# m1-control.net
KiCad netlist of a schematic drawn in EAGLE
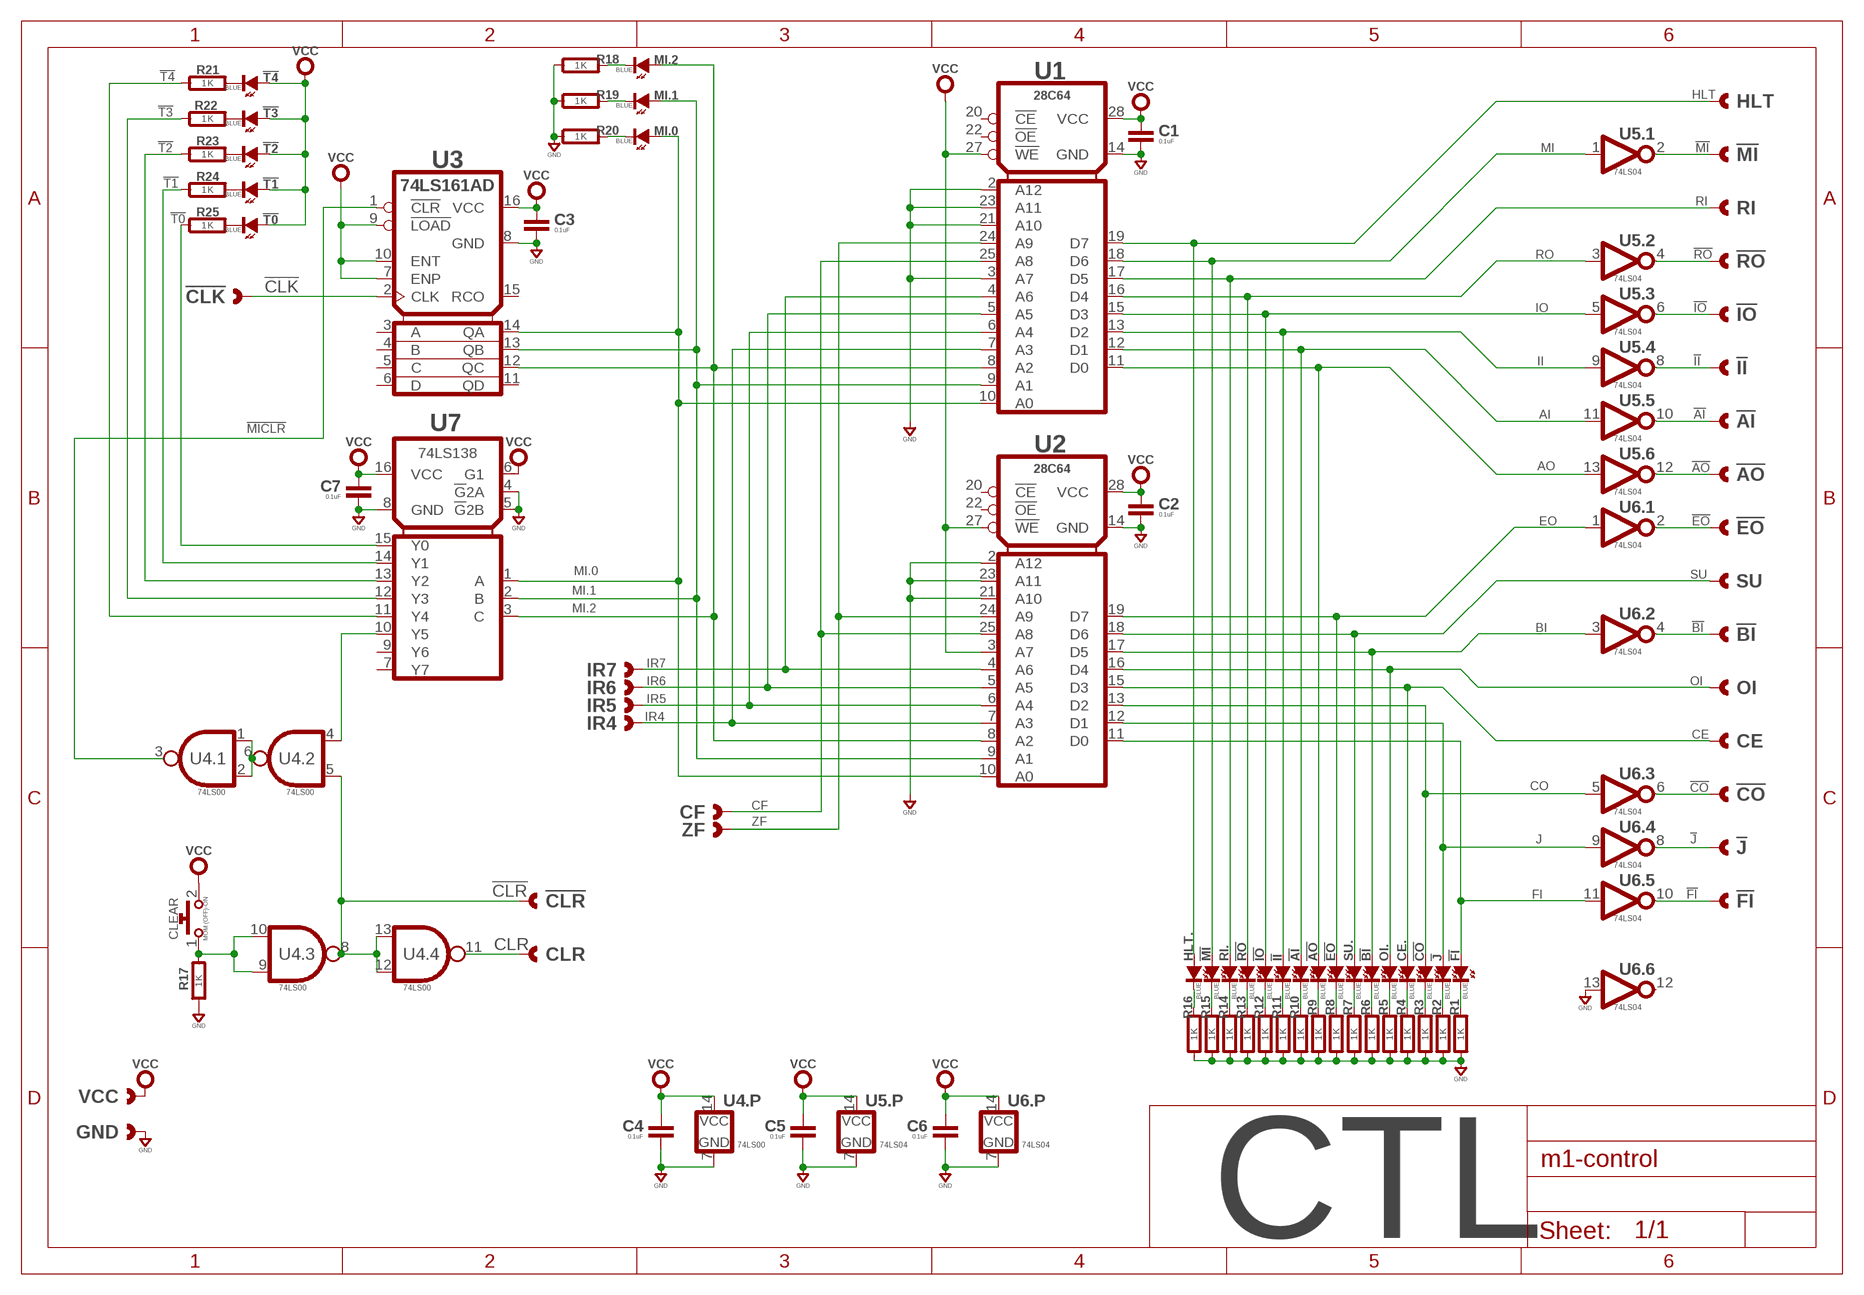
[diagram p0: schematic, sheet 1]

(export (version "E")
  (design (tool "Eeschema 10.0.6"))
  (components
    (comp (ref "!AI")
      (value "CAST-01X1")
      (footprint "eagle-import:CAST01-2.54MM")
      (libsource (lib "eagle-import") (part "CAST-01X1"))
    )
    (comp (ref "!AI!")
      (value "BLUE")
      (footprint "eagle-import:SMD_0603")
      (libsource (lib "eagle-import") (part "SMT0603"))
    )
    (comp (ref "!AO")
      (value "CAST-01X1")
      (footprint "eagle-import:CAST01-2.54MM")
      (libsource (lib "eagle-import") (part "CAST-01X1"))
    )
    (comp (ref "!AO!")
      (value "BLUE")
      (footprint "eagle-import:SMD_0603")
      (libsource (lib "eagle-import") (part "SMT0603"))
    )
    (comp (ref "!BI")
      (value "CAST-01X1")
      (footprint "eagle-import:CAST01-2.54MM")
      (fields (field (name "SPICEPREFIX") "X"))
      (libsource (lib "eagle-import") (part "CAST-01X1"))
    )
    (comp (ref "!BI!")
      (value "BLUE")
      (footprint "eagle-import:SMD_0603")
      (libsource (lib "eagle-import") (part "SMT0603"))
    )
    (comp (ref "!CLK")
      (value "CAST-01X1")
      (footprint "eagle-import:CAST01-2.54MM")
      (libsource (lib "eagle-import") (part "CAST-01X1"))
    )
    (comp (ref "!CLR")
      (value "CAST-01X1")
      (footprint "eagle-import:CAST01-2.54MM")
      (libsource (lib "eagle-import") (part "CAST-01X1"))
    )
    (comp (ref "!CO")
      (value "CAST-01X1")
      (footprint "eagle-import:CAST01-2.54MM")
      (fields (field (name "SPICEPREFIX") "X"))
      (libsource (lib "eagle-import") (part "CAST-01X1"))
    )
    (comp (ref "!CO!")
      (value "BLUE")
      (footprint "eagle-import:SMD_0603")
      (libsource (lib "eagle-import") (part "SMT0603"))
    )
    (comp (ref "!EO")
      (value "CAST-01X1")
      (footprint "eagle-import:CAST01-2.54MM")
      (libsource (lib "eagle-import") (part "CAST-01X1"))
    )
    (comp (ref "!EO!")
      (value "BLUE")
      (footprint "eagle-import:SMD_0603")
      (libsource (lib "eagle-import") (part "SMT0603"))
    )
    (comp (ref "!FI")
      (value "CAST-01X1")
      (footprint "eagle-import:CAST01-2.54MM")
      (fields (field (name "SPICEPREFIX") "X"))
      (libsource (lib "eagle-import") (part "CAST-01X1"))
    )
    (comp (ref "!FI!")
      (value "BLUE")
      (footprint "eagle-import:SMD_0603")
      (libsource (lib "eagle-import") (part "SMT0603"))
    )
    (comp (ref "!II")
      (value "CAST-01X1")
      (footprint "eagle-import:CAST01-2.54MM")
      (libsource (lib "eagle-import") (part "CAST-01X1"))
    )
    (comp (ref "!II!")
      (value "BLUE")
      (footprint "eagle-import:SMD_0603")
      (libsource (lib "eagle-import") (part "SMT0603"))
    )
    (comp (ref "!IO")
      (value "CAST-01X1")
      (footprint "eagle-import:CAST01-2.54MM")
      (libsource (lib "eagle-import") (part "CAST-01X1"))
    )
    (comp (ref "!IO!")
      (value "BLUE")
      (footprint "eagle-import:SMD_0603")
      (libsource (lib "eagle-import") (part "SMT0603"))
    )
    (comp (ref "!J")
      (value "CAST-01X1")
      (footprint "eagle-import:CAST01-2.54MM")
      (fields (field (name "SPICEPREFIX") "X"))
      (libsource (lib "eagle-import") (part "CAST-01X1"))
    )
    (comp (ref "!J!")
      (value "BLUE")
      (footprint "eagle-import:SMD_0603")
      (libsource (lib "eagle-import") (part "SMT0603"))
    )
    (comp (ref "!MI")
      (value "CAST-01X1")
      (footprint "eagle-import:CAST01-2.54MM")
      (libsource (lib "eagle-import") (part "CAST-01X1"))
    )
    (comp (ref "!MI!")
      (value "BLUE")
      (footprint "eagle-import:SMD_0603")
      (libsource (lib "eagle-import") (part "SMT0603"))
    )
    (comp (ref "!RO")
      (value "CAST-01X1")
      (footprint "eagle-import:CAST01-2.54MM")
      (libsource (lib "eagle-import") (part "CAST-01X1"))
    )
    (comp (ref "!RO!")
      (value "BLUE")
      (footprint "eagle-import:SMD_0603")
      (libsource (lib "eagle-import") (part "SMT0603"))
    )
    (comp (ref "!T0")
      (value "BLUE")
      (footprint "eagle-import:SMD_0603")
      (libsource (lib "eagle-import") (part "SMT0603"))
    )
    (comp (ref "!T1")
      (value "BLUE")
      (footprint "eagle-import:SMD_0603")
      (libsource (lib "eagle-import") (part "SMT0603"))
    )
    (comp (ref "!T2")
      (value "BLUE")
      (footprint "eagle-import:SMD_0603")
      (libsource (lib "eagle-import") (part "SMT0603"))
    )
    (comp (ref "!T3")
      (value "BLUE")
      (footprint "eagle-import:SMD_0603")
      (libsource (lib "eagle-import") (part "SMT0603"))
    )
    (comp (ref "!T4")
      (value "BLUE")
      (footprint "eagle-import:SMD_0603")
      (libsource (lib "eagle-import") (part "SMT0603"))
    )
    (comp (ref "C1")
      (value "0.1uF")
      (footprint "eagle-import:0603-CAP")
      (libsource (lib "eagle-import") (part "CAPACITOR0603"))
    )
    (comp (ref "C2")
      (value "0.1uF")
      (footprint "eagle-import:0603-CAP")
      (libsource (lib "eagle-import") (part "CAPACITOR0603"))
    )
    (comp (ref "C3")
      (value "0.1uF")
      (footprint "eagle-import:0603-CAP")
      (libsource (lib "eagle-import") (part "CAPACITOR0603"))
    )
    (comp (ref "C4")
      (value "0.1uF")
      (footprint "eagle-import:0603-CAP")
      (libsource (lib "eagle-import") (part "CAPACITOR0603"))
    )
    (comp (ref "C5")
      (value "0.1uF")
      (footprint "eagle-import:0603-CAP")
      (libsource (lib "eagle-import") (part "CAPACITOR0603"))
    )
    (comp (ref "C6")
      (value "0.1uF")
      (footprint "eagle-import:0603-CAP")
      (libsource (lib "eagle-import") (part "CAPACITOR0603"))
    )
    (comp (ref "C7")
      (value "0.1uF")
      (footprint "eagle-import:0603-CAP")
      (libsource (lib "eagle-import") (part "CAPACITOR0603"))
    )
    (comp (ref "CE")
      (value "CAST-01X1")
      (footprint "eagle-import:CAST01-2.54MM")
      (fields (field (name "SPICEPREFIX") "X"))
      (libsource (lib "eagle-import") (part "CAST-01X1"))
    )
    (comp (ref "CE.")
      (value "BLUE")
      (footprint "eagle-import:SMD_0603")
      (libsource (lib "eagle-import") (part "SMT0603"))
    )
    (comp (ref "CF")
      (value "CAST-01X1")
      (footprint "eagle-import:CAST01-2.54MM")
      (libsource (lib "eagle-import") (part "CAST-01X1"))
    )
    (comp (ref "CLEAR")
      (value "MOM (OFF)-ON")
      (footprint "eagle-import:SWITCH-0635-2P-SMD")
      (fields (field (name "MFR") "CK Switch") (field (name "MPN") "PTS635S*SMTR"))
      (libsource (lib "eagle-import") (part "TACTILE-2PSMD"))
    )
    (comp (ref "CLR")
      (value "CAST-01X1")
      (footprint "eagle-import:CAST01-2.54MM")
      (libsource (lib "eagle-import") (part "CAST-01X1"))
    )
    (comp (ref "GND")
      (value "CAST-01X1")
      (footprint "eagle-import:CAST01-2.54MM")
      (libsource (lib "eagle-import") (part "CAST-01X1"))
    )
    (comp (ref "HLT")
      (value "CAST-01X1")
      (footprint "eagle-import:CAST01-2.54MM")
      (libsource (lib "eagle-import") (part "CAST-01X1"))
    )
    (comp (ref "HLT.")
      (value "BLUE")
      (footprint "eagle-import:SMD_0603")
      (libsource (lib "eagle-import") (part "SMT0603"))
    )
    (comp (ref "IR4")
      (value "CAST-01X1")
      (footprint "eagle-import:CAST01-2.54MM")
      (libsource (lib "eagle-import") (part "CAST-01X1"))
    )
    (comp (ref "IR5")
      (value "CAST-01X1")
      (footprint "eagle-import:CAST01-2.54MM")
      (libsource (lib "eagle-import") (part "CAST-01X1"))
    )
    (comp (ref "IR6")
      (value "CAST-01X1")
      (footprint "eagle-import:CAST01-2.54MM")
      (libsource (lib "eagle-import") (part "CAST-01X1"))
    )
    (comp (ref "IR7")
      (value "CAST-01X1")
      (footprint "eagle-import:CAST01-2.54MM")
      (libsource (lib "eagle-import") (part "CAST-01X1"))
    )
    (comp (ref "MI.0")
      (value "BLUE")
      (footprint "eagle-import:SMD_0603")
      (libsource (lib "eagle-import") (part "SMT0603"))
    )
    (comp (ref "MI.1")
      (value "BLUE")
      (footprint "eagle-import:SMD_0603")
      (libsource (lib "eagle-import") (part "SMT0603"))
    )
    (comp (ref "MI.2")
      (value "BLUE")
      (footprint "eagle-import:SMD_0603")
      (libsource (lib "eagle-import") (part "SMT0603"))
    )
    (comp (ref "OI")
      (value "CAST-01X1")
      (footprint "eagle-import:CAST01-2.54MM")
      (fields (field (name "SPICEPREFIX") "X"))
      (libsource (lib "eagle-import") (part "CAST-01X1"))
    )
    (comp (ref "OI.")
      (value "BLUE")
      (footprint "eagle-import:SMD_0603")
      (libsource (lib "eagle-import") (part "SMT0603"))
    )
    (comp (ref "R1")
      (value "1K")
      (footprint "eagle-import:0603-RES")
      (libsource (lib "eagle-import") (part "RESISTOR0603"))
    )
    (comp (ref "R2")
      (value "1K")
      (footprint "eagle-import:0603-RES")
      (libsource (lib "eagle-import") (part "RESISTOR0603"))
    )
    (comp (ref "R3")
      (value "1K")
      (footprint "eagle-import:0603-RES")
      (libsource (lib "eagle-import") (part "RESISTOR0603"))
    )
    (comp (ref "R4")
      (value "1K")
      (footprint "eagle-import:0603-RES")
      (libsource (lib "eagle-import") (part "RESISTOR0603"))
    )
    (comp (ref "R5")
      (value "1K")
      (footprint "eagle-import:0603-RES")
      (libsource (lib "eagle-import") (part "RESISTOR0603"))
    )
    (comp (ref "R6")
      (value "1K")
      (footprint "eagle-import:0603-RES")
      (libsource (lib "eagle-import") (part "RESISTOR0603"))
    )
    (comp (ref "R7")
      (value "1K")
      (footprint "eagle-import:0603-RES")
      (libsource (lib "eagle-import") (part "RESISTOR0603"))
    )
    (comp (ref "R8")
      (value "1K")
      (footprint "eagle-import:0603-RES")
      (libsource (lib "eagle-import") (part "RESISTOR0603"))
    )
    (comp (ref "R9")
      (value "1K")
      (footprint "eagle-import:0603-RES")
      (libsource (lib "eagle-import") (part "RESISTOR0603"))
    )
    (comp (ref "R10")
      (value "1K")
      (footprint "eagle-import:0603-RES")
      (libsource (lib "eagle-import") (part "RESISTOR0603"))
    )
    (comp (ref "R11")
      (value "1K")
      (footprint "eagle-import:0603-RES")
      (libsource (lib "eagle-import") (part "RESISTOR0603"))
    )
    (comp (ref "R12")
      (value "1K")
      (footprint "eagle-import:0603-RES")
      (libsource (lib "eagle-import") (part "RESISTOR0603"))
    )
    (comp (ref "R13")
      (value "1K")
      (footprint "eagle-import:0603-RES")
      (libsource (lib "eagle-import") (part "RESISTOR0603"))
    )
    (comp (ref "R14")
      (value "1K")
      (footprint "eagle-import:0603-RES")
      (libsource (lib "eagle-import") (part "RESISTOR0603"))
    )
    (comp (ref "R15")
      (value "1K")
      (footprint "eagle-import:0603-RES")
      (libsource (lib "eagle-import") (part "RESISTOR0603"))
    )
    (comp (ref "R16")
      (value "1K")
      (footprint "eagle-import:0603-RES")
      (libsource (lib "eagle-import") (part "RESISTOR0603"))
    )
    (comp (ref "R17")
      (value "1K")
      (footprint "eagle-import:0603-RES")
      (libsource (lib "eagle-import") (part "RESISTOR0603"))
    )
    (comp (ref "R18")
      (value "1K")
      (footprint "eagle-import:0603-RES")
      (libsource (lib "eagle-import") (part "RESISTOR0603"))
    )
    (comp (ref "R19")
      (value "1K")
      (footprint "eagle-import:0603-RES")
      (libsource (lib "eagle-import") (part "RESISTOR0603"))
    )
    (comp (ref "R20")
      (value "1K")
      (footprint "eagle-import:0603-RES")
      (libsource (lib "eagle-import") (part "RESISTOR0603"))
    )
    (comp (ref "R21")
      (value "1K")
      (footprint "eagle-import:0603-RES")
      (libsource (lib "eagle-import") (part "RESISTOR0603"))
    )
    (comp (ref "R22")
      (value "1K")
      (footprint "eagle-import:0603-RES")
      (libsource (lib "eagle-import") (part "RESISTOR0603"))
    )
    (comp (ref "R23")
      (value "1K")
      (footprint "eagle-import:0603-RES")
      (libsource (lib "eagle-import") (part "RESISTOR0603"))
    )
    (comp (ref "R24")
      (value "1K")
      (footprint "eagle-import:0603-RES")
      (libsource (lib "eagle-import") (part "RESISTOR0603"))
    )
    (comp (ref "R25")
      (value "1K")
      (footprint "eagle-import:0603-RES")
      (libsource (lib "eagle-import") (part "RESISTOR0603"))
    )
    (comp (ref "RI")
      (value "CAST-01X1")
      (footprint "eagle-import:CAST01-2.54MM")
      (libsource (lib "eagle-import") (part "CAST-01X1"))
    )
    (comp (ref "RI.")
      (value "BLUE")
      (footprint "eagle-import:SMD_0603")
      (libsource (lib "eagle-import") (part "SMT0603"))
    )
    (comp (ref "SU")
      (value "CAST-01X1")
      (footprint "eagle-import:CAST01-2.54MM")
      (libsource (lib "eagle-import") (part "CAST-01X1"))
    )
    (comp (ref "SU.")
      (value "BLUE")
      (footprint "eagle-import:SMD_0603")
      (libsource (lib "eagle-import") (part "SMT0603"))
    )
    (comp (ref "U1")
      (value "28C64")
      (footprint "eagle-import:SO28")
      (fields (field (name "MFR") "Microchip") (field (name "MPN") "AT28C64B-15SU"))
      (libsource (lib "eagle-import") (part "2864?SC"))
    )
    (comp (ref "U2")
      (value "28C64")
      (footprint "eagle-import:SO28")
      (fields (field (name "MFR") "Microchip") (field (name "MPN") "AT28C64B-15SU"))
      (libsource (lib "eagle-import") (part "2864?SC"))
    )
    (comp (ref "U3")
      (value "74LS161AD")
      (footprint "eagle-import:SO16")
      (libsource (lib "eagle-import") (part "74161A?DLS"))
    )
    (comp (ref "U4")
      (value "74LS00")
      (footprint "eagle-import:SOP14")
      (fields (field (name "MPN") "74LS00N"))
      (libsource (lib "eagle-import") (part "7400?DLS"))
    )
    (comp (ref "U5")
      (value "74LS04")
      (footprint "eagle-import:SOP14")
      (libsource (lib "eagle-import") (part "7404?DLS"))
    )
    (comp (ref "U6")
      (value "74LS04")
      (footprint "eagle-import:SOP14")
      (libsource (lib "eagle-import") (part "7404?DLS"))
    )
    (comp (ref "U7")
      (value "74LS138")
      (footprint "eagle-import:SO16")
      (fields (field (name "MPN") "74LS138D"))
      (libsource (lib "eagle-import") (part "74138?DLS"))
    )
    (comp (ref "VCC")
      (value "CAST-01X1")
      (footprint "eagle-import:CAST01-2.54MM")
      (libsource (lib "eagle-import") (part "CAST-01X1"))
    )
    (comp (ref "ZF")
      (value "CAST-01X1")
      (footprint "eagle-import:CAST01-2.54MM")
      (libsource (lib "eagle-import") (part "CAST-01X1"))
    )
  )
  (nets
    (net (code "1") (name "/AI") (class "Default")
      (node (ref "!AI!") (pin "A") (pinfunction "A_A") (pintype "passive"))
      (node (ref "U1") (pin "12") (pinfunction "D1_12") (pintype "bidirectional"))
      (node (ref "U5") (pin "11") (pinfunction "A_11") (pintype "bidirectional"))
    )
    (net (code "2") (name "/AO") (class "Default")
      (node (ref "!AO!") (pin "A") (pinfunction "A_A") (pintype "passive"))
      (node (ref "U1") (pin "11") (pinfunction "D0_11") (pintype "bidirectional"))
      (node (ref "U5") (pin "13") (pinfunction "A_13") (pintype "bidirectional"))
    )
    (net (code "3") (name "/BI") (class "Default")
      (node (ref "!BI!") (pin "A") (pinfunction "A_A") (pintype "passive"))
      (node (ref "U2") (pin "17") (pinfunction "D5_17") (pintype "bidirectional"))
      (node (ref "U6") (pin "3") (pinfunction "A_3") (pintype "bidirectional"))
    )
    (net (code "4") (name "/CE") (class "Default")
      (node (ref "CE") (pin "1") (pinfunction "1_1") (pintype "bidirectional"))
      (node (ref "CE.") (pin "A") (pinfunction "A_A") (pintype "passive"))
      (node (ref "U2") (pin "15") (pinfunction "D3_15") (pintype "bidirectional"))
    )
    (net (code "5") (name "/CF") (class "Default")
      (node (ref "CF") (pin "1") (pinfunction "1_1") (pintype "bidirectional"))
      (node (ref "U1") (pin "25") (pinfunction "A8_25") (pintype "input"))
      (node (ref "U2") (pin "25") (pinfunction "A8_25") (pintype "input"))
    )
    (net (code "6") (name "/CLR") (class "Default")
      (node (ref "CLR") (pin "1") (pinfunction "1_1") (pintype "bidirectional"))
      (node (ref "U4") (pin "11") (pinfunction "Y_11") (pintype "output"))
    )
    (net (code "7") (name "/CO") (class "Default")
      (node (ref "!CO!") (pin "A") (pinfunction "A_A") (pintype "passive"))
      (node (ref "U2") (pin "13") (pinfunction "D2_13") (pintype "bidirectional"))
      (node (ref "U6") (pin "5") (pinfunction "A_5") (pintype "bidirectional"))
    )
    (net (code "8") (name "/EO") (class "Default")
      (node (ref "!EO!") (pin "A") (pinfunction "A_A") (pintype "passive"))
      (node (ref "U2") (pin "19") (pinfunction "D7_19") (pintype "bidirectional"))
      (node (ref "U6") (pin "1") (pinfunction "A_1") (pintype "bidirectional"))
    )
    (net (code "9") (name "/FI") (class "Default")
      (node (ref "!FI!") (pin "A") (pinfunction "A_A") (pintype "passive"))
      (node (ref "U2") (pin "11") (pinfunction "D0_11") (pintype "bidirectional"))
      (node (ref "U6") (pin "11") (pinfunction "A_11") (pintype "bidirectional"))
    )
    (net (code "10") (name "/HLT") (class "Default")
      (node (ref "HLT") (pin "1") (pinfunction "1_1") (pintype "bidirectional"))
      (node (ref "HLT.") (pin "A") (pinfunction "A_A") (pintype "passive"))
      (node (ref "U1") (pin "19") (pinfunction "D7_19") (pintype "bidirectional"))
    )
    (net (code "11") (name "/II") (class "Default")
      (node (ref "!II!") (pin "A") (pinfunction "A_A") (pintype "passive"))
      (node (ref "U1") (pin "13") (pinfunction "D2_13") (pintype "bidirectional"))
      (node (ref "U5") (pin "9") (pinfunction "A_9") (pintype "bidirectional"))
    )
    (net (code "12") (name "/IO") (class "Default")
      (node (ref "!IO!") (pin "A") (pinfunction "A_A") (pintype "passive"))
      (node (ref "U1") (pin "15") (pinfunction "D3_15") (pintype "bidirectional"))
      (node (ref "U5") (pin "5") (pinfunction "A_5") (pintype "bidirectional"))
    )
    (net (code "13") (name "/IR4") (class "Default")
      (node (ref "IR4") (pin "1") (pinfunction "1_1") (pintype "bidirectional"))
      (node (ref "U1") (pin "7") (pinfunction "A3_7") (pintype "input"))
      (node (ref "U2") (pin "7") (pinfunction "A3_7") (pintype "input"))
    )
    (net (code "14") (name "/IR5") (class "Default")
      (node (ref "IR5") (pin "1") (pinfunction "1_1") (pintype "bidirectional"))
      (node (ref "U1") (pin "6") (pinfunction "A4_6") (pintype "input"))
      (node (ref "U2") (pin "6") (pinfunction "A4_6") (pintype "input"))
    )
    (net (code "15") (name "/IR6") (class "Default")
      (node (ref "IR6") (pin "1") (pinfunction "1_1") (pintype "bidirectional"))
      (node (ref "U1") (pin "5") (pinfunction "A5_5") (pintype "input"))
      (node (ref "U2") (pin "5") (pinfunction "A5_5") (pintype "input"))
    )
    (net (code "16") (name "/IR7") (class "Default")
      (node (ref "IR7") (pin "1") (pinfunction "1_1") (pintype "bidirectional"))
      (node (ref "U1") (pin "4") (pinfunction "A6_4") (pintype "input"))
      (node (ref "U2") (pin "4") (pinfunction "A6_4") (pintype "input"))
    )
    (net (code "17") (name "/J") (class "Default")
      (node (ref "!J!") (pin "A") (pinfunction "A_A") (pintype "passive"))
      (node (ref "U2") (pin "12") (pinfunction "D1_12") (pintype "bidirectional"))
      (node (ref "U6") (pin "9") (pinfunction "A_9") (pintype "bidirectional"))
    )
    (net (code "18") (name "/MI") (class "Default")
      (node (ref "!MI!") (pin "A") (pinfunction "A_A") (pintype "passive"))
      (node (ref "U1") (pin "18") (pinfunction "D6_18") (pintype "bidirectional"))
      (node (ref "U5") (pin "1") (pinfunction "A_1") (pintype "bidirectional"))
    )
    (net (code "19") (name "/MI.0") (class "Default")
      (node (ref "MI.0") (pin "A") (pinfunction "A_A") (pintype "passive"))
      (node (ref "U1") (pin "10") (pinfunction "A0_10") (pintype "input"))
      (node (ref "U2") (pin "10") (pinfunction "A0_10") (pintype "input"))
      (node (ref "U3") (pin "14") (pinfunction "QA_14") (pintype "bidirectional"))
      (node (ref "U7") (pin "1") (pinfunction "A_1") (pintype "input"))
    )
    (net (code "20") (name "/MI.1") (class "Default")
      (node (ref "MI.1") (pin "A") (pinfunction "A_A") (pintype "passive"))
      (node (ref "U1") (pin "9") (pinfunction "A1_9") (pintype "input"))
      (node (ref "U2") (pin "9") (pinfunction "A1_9") (pintype "input"))
      (node (ref "U3") (pin "13") (pinfunction "QB_13") (pintype "bidirectional"))
      (node (ref "U7") (pin "2") (pinfunction "B_2") (pintype "input"))
    )
    (net (code "21") (name "/MI.2") (class "Default")
      (node (ref "MI.2") (pin "A") (pinfunction "A_A") (pintype "passive"))
      (node (ref "U1") (pin "8") (pinfunction "A2_8") (pintype "input"))
      (node (ref "U2") (pin "8") (pinfunction "A2_8") (pintype "input"))
      (node (ref "U3") (pin "12") (pinfunction "QC_12") (pintype "bidirectional"))
      (node (ref "U7") (pin "3") (pinfunction "C_3") (pintype "input"))
    )
    (net (code "22") (name "/OI") (class "Default")
      (node (ref "OI") (pin "1") (pinfunction "1_1") (pintype "bidirectional"))
      (node (ref "OI.") (pin "A") (pinfunction "A_A") (pintype "passive"))
      (node (ref "U2") (pin "16") (pinfunction "D4_16") (pintype "bidirectional"))
    )
    (net (code "23") (name "/RI") (class "Default")
      (node (ref "RI") (pin "1") (pinfunction "1_1") (pintype "bidirectional"))
      (node (ref "RI.") (pin "A") (pinfunction "A_A") (pintype "passive"))
      (node (ref "U1") (pin "17") (pinfunction "D5_17") (pintype "bidirectional"))
    )
    (net (code "24") (name "/RO") (class "Default")
      (node (ref "!RO!") (pin "A") (pinfunction "A_A") (pintype "passive"))
      (node (ref "U1") (pin "16") (pinfunction "D4_16") (pintype "bidirectional"))
      (node (ref "U5") (pin "3") (pinfunction "A_3") (pintype "bidirectional"))
    )
    (net (code "25") (name "/SU") (class "Default")
      (node (ref "SU") (pin "1") (pinfunction "1_1") (pintype "bidirectional"))
      (node (ref "SU.") (pin "A") (pinfunction "A_A") (pintype "passive"))
      (node (ref "U2") (pin "18") (pinfunction "D6_18") (pintype "bidirectional"))
    )
    (net (code "26") (name "/ZF") (class "Default")
      (node (ref "U1") (pin "24") (pinfunction "A9_24") (pintype "input"))
      (node (ref "U2") (pin "24") (pinfunction "A9_24") (pintype "input"))
      (node (ref "ZF") (pin "1") (pinfunction "1_1") (pintype "bidirectional"))
    )
    (net (code "27") (name "/~{AI}") (class "Default")
      (node (ref "!AI") (pin "1") (pinfunction "1_1") (pintype "bidirectional"))
      (node (ref "U5") (pin "10") (pinfunction "Y_10") (pintype "bidirectional"))
    )
    (net (code "28") (name "/~{AO}") (class "Default")
      (node (ref "!AO") (pin "1") (pinfunction "1_1") (pintype "bidirectional"))
      (node (ref "U5") (pin "12") (pinfunction "Y_12") (pintype "bidirectional"))
    )
    (net (code "29") (name "/~{BI}") (class "Default")
      (node (ref "!BI") (pin "1") (pinfunction "1_1") (pintype "bidirectional"))
      (node (ref "U6") (pin "4") (pinfunction "Y_4") (pintype "bidirectional"))
    )
    (net (code "30") (name "/~{CLK}") (class "Default")
      (node (ref "!CLK") (pin "1") (pinfunction "1_1") (pintype "bidirectional"))
      (node (ref "U3") (pin "2") (pinfunction "CLK_2") (pintype "bidirectional"))
    )
    (net (code "31") (name "/~{CLR}") (class "Default")
      (node (ref "!CLR") (pin "1") (pinfunction "1_1") (pintype "bidirectional"))
      (node (ref "U4") (pin "12") (pinfunction "B_12") (pintype "input"))
      (node (ref "U4") (pin "13") (pinfunction "A_13") (pintype "input"))
      (node (ref "U4") (pin "5") (pinfunction "B_5") (pintype "input"))
      (node (ref "U4") (pin "8") (pinfunction "Y_8") (pintype "output"))
    )
    (net (code "32") (name "/~{CO}") (class "Default")
      (node (ref "!CO") (pin "1") (pinfunction "1_1") (pintype "bidirectional"))
      (node (ref "U6") (pin "6") (pinfunction "Y_6") (pintype "bidirectional"))
    )
    (net (code "33") (name "/~{EO}") (class "Default")
      (node (ref "!EO") (pin "1") (pinfunction "1_1") (pintype "bidirectional"))
      (node (ref "U6") (pin "2") (pinfunction "Y_2") (pintype "bidirectional"))
    )
    (net (code "34") (name "/~{FI}") (class "Default")
      (node (ref "!FI") (pin "1") (pinfunction "1_1") (pintype "bidirectional"))
      (node (ref "U6") (pin "10") (pinfunction "Y_10") (pintype "bidirectional"))
    )
    (net (code "35") (name "/~{II}") (class "Default")
      (node (ref "!II") (pin "1") (pinfunction "1_1") (pintype "bidirectional"))
      (node (ref "U5") (pin "8") (pinfunction "Y_8") (pintype "bidirectional"))
    )
    (net (code "36") (name "/~{IO}") (class "Default")
      (node (ref "!IO") (pin "1") (pinfunction "1_1") (pintype "bidirectional"))
      (node (ref "U5") (pin "6") (pinfunction "Y_6") (pintype "bidirectional"))
    )
    (net (code "37") (name "/~{J}") (class "Default")
      (node (ref "!J") (pin "1") (pinfunction "1_1") (pintype "bidirectional"))
      (node (ref "U6") (pin "8") (pinfunction "Y_8") (pintype "bidirectional"))
    )
    (net (code "38") (name "/~{MICLR}") (class "Default")
      (node (ref "U3") (pin "1") (pinfunction "~{CLR}_1") (pintype "bidirectional"))
      (node (ref "U4") (pin "3") (pinfunction "Y_3") (pintype "output"))
    )
    (net (code "39") (name "/~{MI}") (class "Default")
      (node (ref "!MI") (pin "1") (pinfunction "1_1") (pintype "bidirectional"))
      (node (ref "U5") (pin "2") (pinfunction "Y_2") (pintype "bidirectional"))
    )
    (net (code "40") (name "/~{RO}") (class "Default")
      (node (ref "!RO") (pin "1") (pinfunction "1_1") (pintype "bidirectional"))
      (node (ref "U5") (pin "4") (pinfunction "Y_4") (pintype "bidirectional"))
    )
    (net (code "41") (name "/~{T0}") (class "Default")
      (node (ref "R25") (pin "1") (pinfunction "1_1") (pintype "passive"))
      (node (ref "U7") (pin "15") (pinfunction "Y0_15") (pintype "output"))
    )
    (net (code "42") (name "/~{T1}") (class "Default")
      (node (ref "R24") (pin "1") (pinfunction "1_1") (pintype "passive"))
      (node (ref "U7") (pin "14") (pinfunction "Y1_14") (pintype "output"))
    )
    (net (code "43") (name "/~{T2}") (class "Default")
      (node (ref "R23") (pin "1") (pinfunction "1_1") (pintype "passive"))
      (node (ref "U7") (pin "13") (pinfunction "Y2_13") (pintype "output"))
    )
    (net (code "44") (name "/~{T3}") (class "Default")
      (node (ref "R22") (pin "1") (pinfunction "1_1") (pintype "passive"))
      (node (ref "U7") (pin "12") (pinfunction "Y3_12") (pintype "output"))
    )
    (net (code "45") (name "/~{T4}") (class "Default")
      (node (ref "R21") (pin "1") (pinfunction "1_1") (pintype "passive"))
      (node (ref "U7") (pin "11") (pinfunction "Y4_11") (pintype "output"))
    )
    (net (code "46") (name "GND") (class "Default")
      (node (ref "C1") (pin "2") (pinfunction "2_2") (pintype "passive"))
      (node (ref "C2") (pin "2") (pinfunction "2_2") (pintype "passive"))
      (node (ref "C3") (pin "2") (pinfunction "2_2") (pintype "passive"))
      (node (ref "C4") (pin "2") (pinfunction "2_2") (pintype "passive"))
      (node (ref "C5") (pin "2") (pinfunction "2_2") (pintype "passive"))
      (node (ref "C6") (pin "2") (pinfunction "2_2") (pintype "passive"))
      (node (ref "C7") (pin "2") (pinfunction "2_2") (pintype "passive"))
      (node (ref "GND") (pin "1") (pinfunction "1_1") (pintype "bidirectional"))
      (node (ref "R1") (pin "1") (pinfunction "1_1") (pintype "passive"))
      (node (ref "R10") (pin "1") (pinfunction "1_1") (pintype "passive"))
      (node (ref "R11") (pin "1") (pinfunction "1_1") (pintype "passive"))
      (node (ref "R12") (pin "1") (pinfunction "1_1") (pintype "passive"))
      (node (ref "R13") (pin "1") (pinfunction "1_1") (pintype "passive"))
      (node (ref "R14") (pin "1") (pinfunction "1_1") (pintype "passive"))
      (node (ref "R15") (pin "1") (pinfunction "1_1") (pintype "passive"))
      (node (ref "R16") (pin "1") (pinfunction "1_1") (pintype "passive"))
      (node (ref "R17") (pin "1") (pinfunction "1_1") (pintype "passive"))
      (node (ref "R18") (pin "1") (pinfunction "1_1") (pintype "passive"))
      (node (ref "R19") (pin "1") (pinfunction "1_1") (pintype "passive"))
      (node (ref "R2") (pin "1") (pinfunction "1_1") (pintype "passive"))
      (node (ref "R20") (pin "1") (pinfunction "1_1") (pintype "passive"))
      (node (ref "R3") (pin "1") (pinfunction "1_1") (pintype "passive"))
      (node (ref "R4") (pin "1") (pinfunction "1_1") (pintype "passive"))
      (node (ref "R5") (pin "1") (pinfunction "1_1") (pintype "passive"))
      (node (ref "R6") (pin "1") (pinfunction "1_1") (pintype "passive"))
      (node (ref "R7") (pin "1") (pinfunction "1_1") (pintype "passive"))
      (node (ref "R8") (pin "1") (pinfunction "1_1") (pintype "passive"))
      (node (ref "R9") (pin "1") (pinfunction "1_1") (pintype "passive"))
      (node (ref "U1") (pin "14") (pinfunction "GND_14") (pintype "power_in"))
      (node (ref "U1") (pin "2") (pinfunction "A12_2") (pintype "input"))
      (node (ref "U1") (pin "21") (pinfunction "A10_21") (pintype "input"))
      (node (ref "U1") (pin "23") (pinfunction "A11_23") (pintype "input"))
      (node (ref "U1") (pin "3") (pinfunction "A7_3") (pintype "input"))
      (node (ref "U2") (pin "14") (pinfunction "GND_14") (pintype "power_in"))
      (node (ref "U2") (pin "2") (pinfunction "A12_2") (pintype "input"))
      (node (ref "U2") (pin "21") (pinfunction "A10_21") (pintype "input"))
      (node (ref "U2") (pin "23") (pinfunction "A11_23") (pintype "input"))
      (node (ref "U3") (pin "8") (pinfunction "GND_8") (pintype "bidirectional"))
      (node (ref "U4") (pin "7") (pinfunction "GND_7") (pintype "power_in"))
      (node (ref "U5") (pin "7") (pinfunction "GND_7") (pintype "power_in"))
      (node (ref "U6") (pin "13") (pinfunction "A_13") (pintype "bidirectional"))
      (node (ref "U6") (pin "7") (pinfunction "GND_7") (pintype "power_in"))
      (node (ref "U7") (pin "4") (pinfunction "~{G}2A_4") (pintype "input"))
      (node (ref "U7") (pin "5") (pinfunction "~{G}2B_5") (pintype "input"))
      (node (ref "U7") (pin "8") (pinfunction "GND_8") (pintype "power_in"))
    )
    (net (code "47") (name "Net-(!AI!-C)") (class "Default")
      (node (ref "!AI!") (pin "K") (pinfunction "C_K") (pintype "passive"))
      (node (ref "R10") (pin "2") (pinfunction "2_2") (pintype "passive"))
    )
    (net (code "48") (name "Net-(!AO!-C)") (class "Default")
      (node (ref "!AO!") (pin "K") (pinfunction "C_K") (pintype "passive"))
      (node (ref "R9") (pin "2") (pinfunction "2_2") (pintype "passive"))
    )
    (net (code "49") (name "Net-(!BI!-C)") (class "Default")
      (node (ref "!BI!") (pin "K") (pinfunction "C_K") (pintype "passive"))
      (node (ref "R6") (pin "2") (pinfunction "2_2") (pintype "passive"))
    )
    (net (code "50") (name "Net-(!CO!-C)") (class "Default")
      (node (ref "!CO!") (pin "K") (pinfunction "C_K") (pintype "passive"))
      (node (ref "R3") (pin "2") (pinfunction "2_2") (pintype "passive"))
    )
    (net (code "51") (name "Net-(!EO!-C)") (class "Default")
      (node (ref "!EO!") (pin "K") (pinfunction "C_K") (pintype "passive"))
      (node (ref "R8") (pin "2") (pinfunction "2_2") (pintype "passive"))
    )
    (net (code "52") (name "Net-(!FI!-C)") (class "Default")
      (node (ref "!FI!") (pin "K") (pinfunction "C_K") (pintype "passive"))
      (node (ref "R1") (pin "2") (pinfunction "2_2") (pintype "passive"))
    )
    (net (code "53") (name "Net-(!II!-C)") (class "Default")
      (node (ref "!II!") (pin "K") (pinfunction "C_K") (pintype "passive"))
      (node (ref "R11") (pin "2") (pinfunction "2_2") (pintype "passive"))
    )
    (net (code "54") (name "Net-(!IO!-C)") (class "Default")
      (node (ref "!IO!") (pin "K") (pinfunction "C_K") (pintype "passive"))
      (node (ref "R12") (pin "2") (pinfunction "2_2") (pintype "passive"))
    )
    (net (code "55") (name "Net-(!J!-C)") (class "Default")
      (node (ref "!J!") (pin "K") (pinfunction "C_K") (pintype "passive"))
      (node (ref "R2") (pin "2") (pinfunction "2_2") (pintype "passive"))
    )
    (net (code "56") (name "Net-(!MI!-C)") (class "Default")
      (node (ref "!MI!") (pin "K") (pinfunction "C_K") (pintype "passive"))
      (node (ref "R15") (pin "2") (pinfunction "2_2") (pintype "passive"))
    )
    (net (code "57") (name "Net-(!RO!-C)") (class "Default")
      (node (ref "!RO!") (pin "K") (pinfunction "C_K") (pintype "passive"))
      (node (ref "R13") (pin "2") (pinfunction "2_2") (pintype "passive"))
    )
    (net (code "58") (name "Net-(!T0-C)") (class "Default")
      (node (ref "!T0") (pin "K") (pinfunction "C_K") (pintype "passive"))
      (node (ref "R25") (pin "2") (pinfunction "2_2") (pintype "passive"))
    )
    (net (code "59") (name "Net-(!T1-C)") (class "Default")
      (node (ref "!T1") (pin "K") (pinfunction "C_K") (pintype "passive"))
      (node (ref "R24") (pin "2") (pinfunction "2_2") (pintype "passive"))
    )
    (net (code "60") (name "Net-(!T2-C)") (class "Default")
      (node (ref "!T2") (pin "K") (pinfunction "C_K") (pintype "passive"))
      (node (ref "R23") (pin "2") (pinfunction "2_2") (pintype "passive"))
    )
    (net (code "61") (name "Net-(!T3-C)") (class "Default")
      (node (ref "!T3") (pin "K") (pinfunction "C_K") (pintype "passive"))
      (node (ref "R22") (pin "2") (pinfunction "2_2") (pintype "passive"))
    )
    (net (code "62") (name "Net-(!T4-C)") (class "Default")
      (node (ref "!T4") (pin "K") (pinfunction "C_K") (pintype "passive"))
      (node (ref "R21") (pin "2") (pinfunction "2_2") (pintype "passive"))
    )
    (net (code "63") (name "Net-(CE.-C)") (class "Default")
      (node (ref "CE.") (pin "K") (pinfunction "C_K") (pintype "passive"))
      (node (ref "R4") (pin "2") (pinfunction "2_2") (pintype "passive"))
    )
    (net (code "64") (name "Net-(HLT.-C)") (class "Default")
      (node (ref "HLT.") (pin "K") (pinfunction "C_K") (pintype "passive"))
      (node (ref "R16") (pin "2") (pinfunction "2_2") (pintype "passive"))
    )
    (net (code "65") (name "Net-(MI.0-C)") (class "Default")
      (node (ref "MI.0") (pin "K") (pinfunction "C_K") (pintype "passive"))
      (node (ref "R20") (pin "2") (pinfunction "2_2") (pintype "passive"))
    )
    (net (code "66") (name "Net-(MI.1-C)") (class "Default")
      (node (ref "MI.1") (pin "K") (pinfunction "C_K") (pintype "passive"))
      (node (ref "R19") (pin "2") (pinfunction "2_2") (pintype "passive"))
    )
    (net (code "67") (name "Net-(MI.2-C)") (class "Default")
      (node (ref "MI.2") (pin "K") (pinfunction "C_K") (pintype "passive"))
      (node (ref "R18") (pin "2") (pinfunction "2_2") (pintype "passive"))
    )
    (net (code "68") (name "Net-(OI.-C)") (class "Default")
      (node (ref "OI.") (pin "K") (pinfunction "C_K") (pintype "passive"))
      (node (ref "R5") (pin "2") (pinfunction "2_2") (pintype "passive"))
    )
    (net (code "69") (name "Net-(RI.-C)") (class "Default")
      (node (ref "R14") (pin "2") (pinfunction "2_2") (pintype "passive"))
      (node (ref "RI.") (pin "K") (pinfunction "C_K") (pintype "passive"))
    )
    (net (code "70") (name "Net-(SU.-C)") (class "Default")
      (node (ref "R7") (pin "2") (pinfunction "2_2") (pintype "passive"))
      (node (ref "SU.") (pin "K") (pinfunction "C_K") (pintype "passive"))
    )
    (net (code "71") (name "Net-(U4A-A)") (class "Default")
      (node (ref "U4") (pin "1") (pinfunction "A_1") (pintype "input"))
      (node (ref "U4") (pin "2") (pinfunction "B_2") (pintype "input"))
      (node (ref "U4") (pin "6") (pinfunction "Y_6") (pintype "output"))
    )
    (net (code "72") (name "Net-(U4B-A)") (class "Default")
      (node (ref "U4") (pin "4") (pinfunction "A_4") (pintype "input"))
      (node (ref "U7") (pin "10") (pinfunction "Y5_10") (pintype "output"))
    )
    (net (code "73") (name "Net-(U4C-A)") (class "Default")
      (node (ref "CLEAR") (pin "1") (pinfunction "1_1") (pintype "bidirectional"))
      (node (ref "R17") (pin "2") (pinfunction "2_2") (pintype "passive"))
      (node (ref "U4") (pin "10") (pinfunction "A_10") (pintype "input"))
      (node (ref "U4") (pin "9") (pinfunction "B_9") (pintype "input"))
    )
    (net (code "74") (name "VCC") (class "Default")
      (node (ref "!T0") (pin "A") (pinfunction "A_A") (pintype "passive"))
      (node (ref "!T1") (pin "A") (pinfunction "A_A") (pintype "passive"))
      (node (ref "!T2") (pin "A") (pinfunction "A_A") (pintype "passive"))
      (node (ref "!T3") (pin "A") (pinfunction "A_A") (pintype "passive"))
      (node (ref "!T4") (pin "A") (pinfunction "A_A") (pintype "passive"))
      (node (ref "C1") (pin "1") (pinfunction "1_1") (pintype "passive"))
      (node (ref "C2") (pin "1") (pinfunction "1_1") (pintype "passive"))
      (node (ref "C3") (pin "1") (pinfunction "1_1") (pintype "passive"))
      (node (ref "C4") (pin "1") (pinfunction "1_1") (pintype "passive"))
      (node (ref "C5") (pin "1") (pinfunction "1_1") (pintype "passive"))
      (node (ref "C6") (pin "1") (pinfunction "1_1") (pintype "passive"))
      (node (ref "C7") (pin "1") (pinfunction "1_1") (pintype "passive"))
      (node (ref "CLEAR") (pin "2") (pinfunction "2_2") (pintype "bidirectional"))
      (node (ref "U1") (pin "27") (pinfunction "~{WE}_27") (pintype "input"))
      (node (ref "U1") (pin "28") (pinfunction "VCC_28") (pintype "power_in"))
      (node (ref "U2") (pin "27") (pinfunction "~{WE}_27") (pintype "input"))
      (node (ref "U2") (pin "28") (pinfunction "VCC_28") (pintype "power_in"))
      (node (ref "U2") (pin "3") (pinfunction "A7_3") (pintype "input"))
      (node (ref "U3") (pin "10") (pinfunction "ENT_10") (pintype "bidirectional"))
      (node (ref "U3") (pin "16") (pinfunction "VCC_16") (pintype "bidirectional"))
      (node (ref "U3") (pin "7") (pinfunction "ENP_7") (pintype "bidirectional"))
      (node (ref "U3") (pin "9") (pinfunction "~{LOAD}_9") (pintype "bidirectional"))
      (node (ref "U4") (pin "14") (pinfunction "VCC_14") (pintype "power_in"))
      (node (ref "U5") (pin "14") (pinfunction "VCC_14") (pintype "power_in"))
      (node (ref "U6") (pin "14") (pinfunction "VCC_14") (pintype "power_in"))
      (node (ref "U7") (pin "16") (pinfunction "VCC_16") (pintype "power_in"))
      (node (ref "U7") (pin "6") (pinfunction "G1_6") (pintype "input"))
      (node (ref "VCC") (pin "1") (pinfunction "1_1") (pintype "bidirectional"))
    )
    (net (code "75") (name "unconnected-(U1-~{CE}-Pad20)") (class "Default")
      (node (ref "U1") (pin "20") (pinfunction "~{CE}_20") (pintype "input"))
    )
    (net (code "76") (name "unconnected-(U1-~{OE}-Pad22)") (class "Default")
      (node (ref "U1") (pin "22") (pinfunction "~{OE}_22") (pintype "input"))
    )
    (net (code "77") (name "unconnected-(U2-~{CE}-Pad20)") (class "Default")
      (node (ref "U2") (pin "20") (pinfunction "~{CE}_20") (pintype "input"))
    )
    (net (code "78") (name "unconnected-(U2-~{OE}-Pad22)") (class "Default")
      (node (ref "U2") (pin "22") (pinfunction "~{OE}_22") (pintype "input"))
    )
    (net (code "79") (name "unconnected-(U3-A-Pad3)") (class "Default")
      (node (ref "U3") (pin "3") (pinfunction "A_3") (pintype "bidirectional"))
    )
    (net (code "80") (name "unconnected-(U3-B-Pad4)") (class "Default")
      (node (ref "U3") (pin "4") (pinfunction "B_4") (pintype "bidirectional"))
    )
    (net (code "81") (name "unconnected-(U3-C-Pad5)") (class "Default")
      (node (ref "U3") (pin "5") (pinfunction "C_5") (pintype "bidirectional"))
    )
    (net (code "82") (name "unconnected-(U3-D-Pad6)") (class "Default")
      (node (ref "U3") (pin "6") (pinfunction "D_6") (pintype "bidirectional"))
    )
    (net (code "83") (name "unconnected-(U3-QD-Pad11)") (class "Default")
      (node (ref "U3") (pin "11") (pinfunction "QD_11") (pintype "bidirectional"))
    )
    (net (code "84") (name "unconnected-(U3-RCO-Pad15)") (class "Default")
      (node (ref "U3") (pin "15") (pinfunction "RCO_15") (pintype "bidirectional"))
    )
    (net (code "85") (name "unconnected-(U6F-Y-Pad12)") (class "Default")
      (node (ref "U6") (pin "12") (pinfunction "Y_12") (pintype "bidirectional"))
    )
    (net (code "86") (name "unconnected-(U7-Y6-Pad9)") (class "Default")
      (node (ref "U7") (pin "9") (pinfunction "Y6_9") (pintype "output"))
    )
    (net (code "87") (name "unconnected-(U7-Y7-Pad7)") (class "Default")
      (node (ref "U7") (pin "7") (pinfunction "Y7_7") (pintype "output"))
    )
  )
)
